# MAGI_sPrototypeBoard.net
KiCad netlist of a schematic drawn in Altium Designer
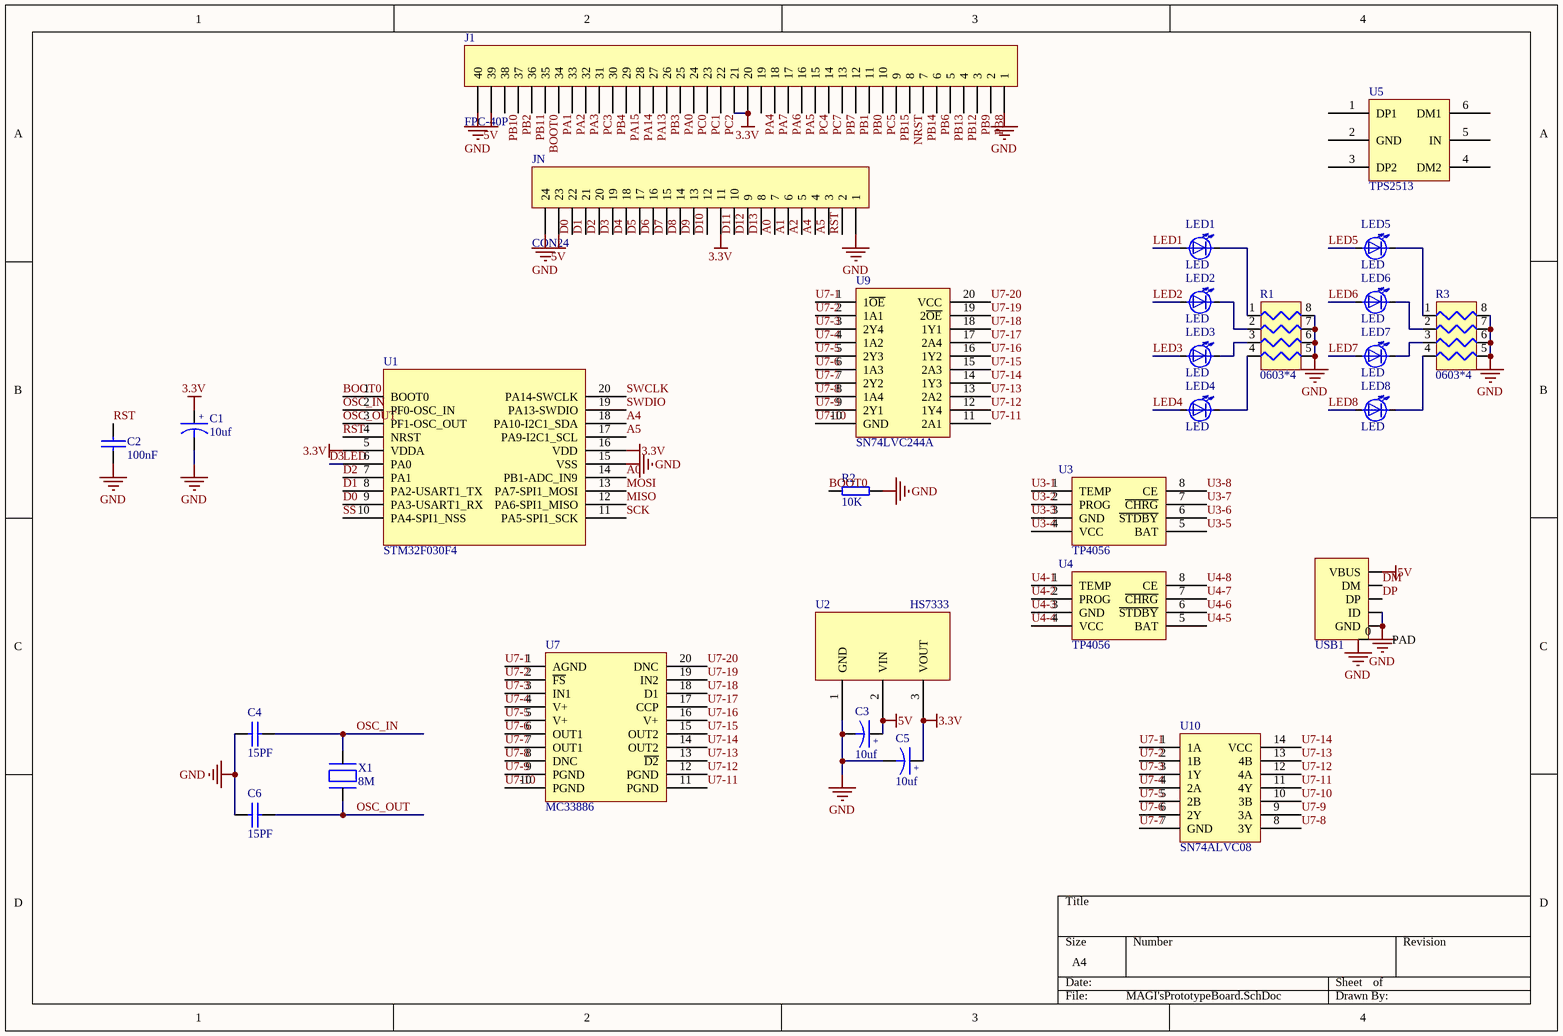
[diagram p0: MAGI'sPrototypeBoard.SchDoc]

(export (version "E")
  (design (tool "Eeschema 10.0.6"))
  (components
    (comp (ref "C1")
      (value "10uf")
      (footprint "6-0805_n")
      (description "Capacitor")
      (libsource (lib "电容器") (part "CAPACITOR POL"))
    )
    (comp (ref "C2") (value "100nF") (footprint "6-0805_n") (libsource (lib "STM32") (part "CAP")))
    (comp (ref "C3")
      (value "10uf")
      (footprint "6-0805_n")
      (description "Capacitor")
      (libsource (lib "电容器") (part "CAPACITOR POL"))
    )
    (comp (ref "C4") (value "15PF") (footprint "6-0805_n") (libsource (lib "STM32") (part "CAP")))
    (comp (ref "C5")
      (value "10uf")
      (footprint "6-0805_n")
      (description "Capacitor")
      (libsource (lib "电容器") (part "CAPACITOR POL"))
    )
    (comp (ref "C6") (value "15PF") (footprint "6-0805_n") (libsource (lib "STM32") (part "CAP")))
    (comp (ref "J1")
      (value "FPC-40P")
      (footprint "FFC/SM0.5-2H40")
      (description "Connector")
      (libsource (lib "CON系列") (part "CON40"))
    )
    (comp (ref "JN")
      (value "CON24")
      (footprint "FFC/SM0.5-2H24")
      (description "Connector")
      (libsource (lib "CON系列") (part "CON24"))
    )
    (comp (ref "LED1") (value "LED") (footprint "6-0805_N") (libsource (lib "二极管") (part "LED_3")))
    (comp (ref "LED2") (value "LED") (footprint "6-0805_N") (libsource (lib "二极管") (part "LED_3")))
    (comp (ref "LED3") (value "LED") (footprint "6-0805_N") (libsource (lib "二极管") (part "LED_3")))
    (comp (ref "LED4") (value "LED") (footprint "6-0805_N") (libsource (lib "二极管") (part "LED_3")))
    (comp (ref "LED5") (value "LED") (footprint "6-0805_N") (libsource (lib "二极管") (part "LED_3")))
    (comp (ref "LED6") (value "LED") (footprint "6-0805_N") (libsource (lib "二极管") (part "LED_3")))
    (comp (ref "LED7") (value "LED") (footprint "6-0805_N") (libsource (lib "二极管") (part "LED_3")))
    (comp (ref "LED8") (value "LED") (footprint "6-0805_N") (libsource (lib "二极管") (part "LED_3")))
    (comp (ref "R1") (value "0603*4") (footprint "0603*4") (libsource (lib "Res") (part "0603*4")))
    (comp (ref "R2") (value "10K") (footprint "6-0805_n") (libsource (lib "STM32") (part "RES")))
    (comp (ref "R3") (value "0603*4") (footprint "0603*4") (libsource (lib "Res") (part "0603*4")))
    (comp (ref "U1")
      (value "STM32F030F4")
      (footprint "STM32F030")
      (libsource (lib "MCU") (part "STM32F030F4"))
    )
    (comp (ref "U2") (value "HS7333") (footprint "HS7333") (libsource (lib "PMIC") (part "HS7333")))
    (comp (ref "U3") (value "TP4056") (footprint "TP4056") (libsource (lib "PMIC") (part "TP4056")))
    (comp (ref "U4") (value "TP4056") (footprint "TP4056") (libsource (lib "PMIC") (part "TP4056")))
    (comp (ref "U5") (value "TPS2513") (footprint "TPS2513") (libsource (lib "PMIC") (part "TPS2513")))
    (comp (ref "U7") (value "MC33886") (footprint "MC33886") (libsource (lib "PMIC") (part "MC33886")))
    (comp (ref "U9")
      (value "SN74LVC244A")
      (footprint "TPS61030PWP")
      (libsource (lib "LogicIC") (part "74LVC244"))
    )
    (comp (ref "U10")
      (value "SN74ALVC08")
      (footprint "SN74ALVC08D")
      (libsource (lib "LogicIC") (part "SN74ALVC08"))
    )
    (comp (ref "USB1")
      (value "USB_Micro")
      (footprint "USB:MicroUSB-B")
      (description "USB")
      (libsource (lib "SCH_USB") (part "USB_Micro"))
    )
    (comp (ref "X1") (value "8M") (footprint "5032") (libsource (lib "STM32") (part "CRYSTAL")))
  )
  (nets
    (net (code "1") (name "/A0") (class "Default")
      (node (ref "JN") (pin "7") (pinfunction "7_7") (pintype "passive"))
      (node (ref "U1") (pin "14") (pinfunction "PB1-ADC_IN9_14") (pintype "passive"))
    )
    (net (code "2") (name "/A1") (class "Default")
      (node (ref "JN") (pin "6") (pinfunction "6_6") (pintype "passive"))
    )
    (net (code "3") (name "/A2") (class "Default")
      (node (ref "JN") (pin "5") (pinfunction "5_5") (pintype "passive"))
    )
    (net (code "4") (name "/A4") (class "Default")
      (node (ref "JN") (pin "4") (pinfunction "4_4") (pintype "passive"))
      (node (ref "U1") (pin "18") (pinfunction "PA10-I2C1_SDA_18") (pintype "passive"))
    )
    (net (code "5") (name "/A5") (class "Default")
      (node (ref "JN") (pin "3") (pinfunction "3_3") (pintype "passive"))
      (node (ref "U1") (pin "17") (pinfunction "PA9-I2C1_SCL_17") (pintype "passive"))
    )
    (net (code "6") (name "/BOOT0") (class "Default")
      (node (ref "J1") (pin "35") (pinfunction "35_35") (pintype "passive"))
      (node (ref "R2") (pin "2") (pinfunction "2_2") (pintype "passive"))
      (node (ref "U1") (pin "1") (pinfunction "BOOT0_1") (pintype "passive"))
    )
    (net (code "7") (name "/D0") (class "Default")
      (node (ref "JN") (pin "22") (pinfunction "22_22") (pintype "passive"))
      (node (ref "U1") (pin "9") (pinfunction "PA3-USART1_RX_9") (pintype "passive"))
    )
    (net (code "8") (name "/D1") (class "Default")
      (node (ref "JN") (pin "21") (pinfunction "21_21") (pintype "passive"))
      (node (ref "U1") (pin "8") (pinfunction "PA2-USART1_TX_8") (pintype "passive"))
    )
    (net (code "9") (name "/D2") (class "Default")
      (node (ref "JN") (pin "20") (pinfunction "20_20") (pintype "passive"))
      (node (ref "U1") (pin "7") (pinfunction "PA1_7") (pintype "passive"))
    )
    (net (code "10") (name "/D3") (class "Default")
      (node (ref "JN") (pin "19") (pinfunction "19_19") (pintype "passive"))
      (node (ref "U1") (pin "6") (pinfunction "PA0_6") (pintype "passive"))
    )
    (net (code "11") (name "/D4") (class "Default")
      (node (ref "JN") (pin "18") (pinfunction "18_18") (pintype "passive"))
    )
    (net (code "12") (name "/D5") (class "Default")
      (node (ref "JN") (pin "17") (pinfunction "17_17") (pintype "passive"))
    )
    (net (code "13") (name "/D6") (class "Default")
      (node (ref "JN") (pin "16") (pinfunction "16_16") (pintype "passive"))
    )
    (net (code "14") (name "/D7") (class "Default")
      (node (ref "JN") (pin "15") (pinfunction "15_15") (pintype "passive"))
    )
    (net (code "15") (name "/D8") (class "Default")
      (node (ref "JN") (pin "14") (pinfunction "14_14") (pintype "passive"))
    )
    (net (code "16") (name "/D9") (class "Default")
      (node (ref "JN") (pin "13") (pinfunction "13_13") (pintype "passive"))
    )
    (net (code "17") (name "/D10") (class "Default")
      (node (ref "JN") (pin "12") (pinfunction "12_12") (pintype "passive"))
    )
    (net (code "18") (name "/D11") (class "Default")
      (node (ref "JN") (pin "10") (pinfunction "10_10") (pintype "passive"))
    )
    (net (code "19") (name "/D12") (class "Default")
      (node (ref "JN") (pin "9") (pinfunction "9_9") (pintype "passive"))
    )
    (net (code "20") (name "/D13") (class "Default")
      (node (ref "JN") (pin "8") (pinfunction "8_8") (pintype "passive"))
    )
    (net (code "21") (name "/DM") (class "Default")
      (node (ref "USB1") (pin "2") (pinfunction "DM_2") (pintype "passive"))
    )
    (net (code "22") (name "/DP") (class "Default")
      (node (ref "USB1") (pin "3") (pinfunction "DP_3") (pintype "passive"))
    )
    (net (code "23") (name "/LED1") (class "Default")
      (node (ref "LED1") (pin "1") (pinfunction "A_1") (pintype "passive"))
    )
    (net (code "24") (name "/LED2") (class "Default")
      (node (ref "LED2") (pin "1") (pinfunction "A_1") (pintype "passive"))
    )
    (net (code "25") (name "/LED3") (class "Default")
      (node (ref "LED3") (pin "1") (pinfunction "A_1") (pintype "passive"))
    )
    (net (code "26") (name "/LED4") (class "Default")
      (node (ref "LED4") (pin "1") (pinfunction "A_1") (pintype "passive"))
    )
    (net (code "27") (name "/LED5") (class "Default")
      (node (ref "LED5") (pin "1") (pinfunction "A_1") (pintype "passive"))
    )
    (net (code "28") (name "/LED6") (class "Default")
      (node (ref "LED6") (pin "1") (pinfunction "A_1") (pintype "passive"))
    )
    (net (code "29") (name "/LED7") (class "Default")
      (node (ref "LED7") (pin "1") (pinfunction "A_1") (pintype "passive"))
    )
    (net (code "30") (name "/LED8") (class "Default")
      (node (ref "LED8") (pin "1") (pinfunction "A_1") (pintype "passive"))
    )
    (net (code "31") (name "/MISO") (class "Default")
      (node (ref "U1") (pin "12") (pinfunction "PA6-SPI1_MISO_12") (pintype "passive"))
    )
    (net (code "32") (name "/MOSI") (class "Default")
      (node (ref "U1") (pin "13") (pinfunction "PA7-SPI1_MOSI_13") (pintype "passive"))
    )
    (net (code "33") (name "/NRST") (class "Default")
      (node (ref "J1") (pin "8") (pinfunction "8_8") (pintype "passive"))
    )
    (net (code "34") (name "/OSC_IN") (class "Default")
      (node (ref "C4") (pin "2") (pinfunction "2_2") (pintype "passive"))
      (node (ref "U1") (pin "2") (pinfunction "PF0-OSC_IN_2") (pintype "passive"))
      (node (ref "X1") (pin "1") (pinfunction "1_1") (pintype "passive"))
    )
    (net (code "35") (name "/OSC_OUT") (class "Default")
      (node (ref "C6") (pin "2") (pinfunction "2_2") (pintype "passive"))
      (node (ref "U1") (pin "3") (pinfunction "PF1-OSC_OUT_3") (pintype "passive"))
      (node (ref "X1") (pin "2") (pinfunction "2_2") (pintype "passive"))
    )
    (net (code "36") (name "/PA0") (class "Default")
      (node (ref "J1") (pin "25") (pinfunction "25_25") (pintype "passive"))
    )
    (net (code "37") (name "/PA1") (class "Default")
      (node (ref "J1") (pin "34") (pinfunction "34_34") (pintype "passive"))
    )
    (net (code "38") (name "/PA2") (class "Default")
      (node (ref "J1") (pin "33") (pinfunction "33_33") (pintype "passive"))
    )
    (net (code "39") (name "/PA3") (class "Default")
      (node (ref "J1") (pin "32") (pinfunction "32_32") (pintype "passive"))
    )
    (net (code "40") (name "/PA4") (class "Default")
      (node (ref "J1") (pin "19") (pinfunction "19_19") (pintype "passive"))
    )
    (net (code "41") (name "/PA5") (class "Default")
      (node (ref "J1") (pin "16") (pinfunction "16_16") (pintype "passive"))
    )
    (net (code "42") (name "/PA6") (class "Default")
      (node (ref "J1") (pin "17") (pinfunction "17_17") (pintype "passive"))
    )
    (net (code "43") (name "/PA7") (class "Default")
      (node (ref "J1") (pin "18") (pinfunction "18_18") (pintype "passive"))
    )
    (net (code "44") (name "/PA13") (class "Default")
      (node (ref "J1") (pin "27") (pinfunction "27_27") (pintype "passive"))
    )
    (net (code "45") (name "/PA14") (class "Default")
      (node (ref "J1") (pin "28") (pinfunction "28_28") (pintype "passive"))
    )
    (net (code "46") (name "/PA15") (class "Default")
      (node (ref "J1") (pin "29") (pinfunction "29_29") (pintype "passive"))
    )
    (net (code "47") (name "/PB0") (class "Default")
      (node (ref "J1") (pin "11") (pinfunction "11_11") (pintype "passive"))
    )
    (net (code "48") (name "/PB1") (class "Default")
      (node (ref "J1") (pin "12") (pinfunction "12_12") (pintype "passive"))
    )
    (net (code "49") (name "/PB2") (class "Default")
      (node (ref "J1") (pin "37") (pinfunction "37_37") (pintype "passive"))
    )
    (net (code "50") (name "/PB3") (class "Default")
      (node (ref "J1") (pin "26") (pinfunction "26_26") (pintype "passive"))
    )
    (net (code "51") (name "/PB4") (class "Default")
      (node (ref "J1") (pin "30") (pinfunction "30_30") (pintype "passive"))
    )
    (net (code "52") (name "/PB6") (class "Default")
      (node (ref "J1") (pin "6") (pinfunction "6_6") (pintype "passive"))
    )
    (net (code "53") (name "/PB7") (class "Default")
      (node (ref "J1") (pin "13") (pinfunction "13_13") (pintype "passive"))
    )
    (net (code "54") (name "/PB8") (class "Default")
      (node (ref "J1") (pin "2") (pinfunction "2_2") (pintype "passive"))
    )
    (net (code "55") (name "/PB9") (class "Default")
      (node (ref "J1") (pin "3") (pinfunction "3_3") (pintype "passive"))
    )
    (net (code "56") (name "/PB10") (class "Default")
      (node (ref "J1") (pin "38") (pinfunction "38_38") (pintype "passive"))
    )
    (net (code "57") (name "/PB11") (class "Default")
      (node (ref "J1") (pin "36") (pinfunction "36_36") (pintype "passive"))
    )
    (net (code "58") (name "/PB12") (class "Default")
      (node (ref "J1") (pin "4") (pinfunction "4_4") (pintype "passive"))
    )
    (net (code "59") (name "/PB13") (class "Default")
      (node (ref "J1") (pin "5") (pinfunction "5_5") (pintype "passive"))
    )
    (net (code "60") (name "/PB14") (class "Default")
      (node (ref "J1") (pin "7") (pinfunction "7_7") (pintype "passive"))
    )
    (net (code "61") (name "/PB15") (class "Default")
      (node (ref "J1") (pin "9") (pinfunction "9_9") (pintype "passive"))
    )
    (net (code "62") (name "/PC0") (class "Default")
      (node (ref "J1") (pin "24") (pinfunction "24_24") (pintype "passive"))
    )
    (net (code "63") (name "/PC1") (class "Default")
      (node (ref "J1") (pin "23") (pinfunction "23_23") (pintype "passive"))
    )
    (net (code "64") (name "/PC2") (class "Default")
      (node (ref "J1") (pin "22") (pinfunction "22_22") (pintype "passive"))
    )
    (net (code "65") (name "/PC3") (class "Default")
      (node (ref "J1") (pin "31") (pinfunction "31_31") (pintype "passive"))
    )
    (net (code "66") (name "/PC4") (class "Default")
      (node (ref "J1") (pin "15") (pinfunction "15_15") (pintype "passive"))
    )
    (net (code "67") (name "/PC5") (class "Default")
      (node (ref "J1") (pin "10") (pinfunction "10_10") (pintype "passive"))
    )
    (net (code "68") (name "/PC7") (class "Default")
      (node (ref "J1") (pin "14") (pinfunction "14_14") (pintype "passive"))
    )
    (net (code "69") (name "/RST") (class "Default")
      (node (ref "C2") (pin "2") (pinfunction "2_2") (pintype "passive"))
      (node (ref "JN") (pin "2") (pinfunction "2_2") (pintype "passive"))
      (node (ref "U1") (pin "4") (pinfunction "NRST_4") (pintype "passive"))
    )
    (net (code "70") (name "/SCK") (class "Default")
      (node (ref "U1") (pin "11") (pinfunction "PA5-SPI1_SCK_11") (pintype "passive"))
    )
    (net (code "71") (name "/SS") (class "Default")
      (node (ref "U1") (pin "10") (pinfunction "PA4-SPI1_NSS_10") (pintype "passive"))
    )
    (net (code "72") (name "/SWCLK") (class "Default")
      (node (ref "U1") (pin "20") (pinfunction "PA14-SWCLK_20") (pintype "passive"))
    )
    (net (code "73") (name "/SWDIO") (class "Default")
      (node (ref "U1") (pin "19") (pinfunction "PA13-SWDIO_19") (pintype "passive"))
    )
    (net (code "74") (name "/U3-1") (class "Default")
      (node (ref "U3") (pin "1") (pinfunction "TEMP_1") (pintype "passive"))
    )
    (net (code "75") (name "/U3-2") (class "Default")
      (node (ref "U3") (pin "2") (pinfunction "PROG_2") (pintype "passive"))
    )
    (net (code "76") (name "/U3-3") (class "Default")
      (node (ref "U3") (pin "3") (pinfunction "GND_3") (pintype "passive"))
    )
    (net (code "77") (name "/U3-4") (class "Default")
      (node (ref "U3") (pin "4") (pinfunction "VCC_4") (pintype "passive"))
    )
    (net (code "78") (name "/U3-5") (class "Default")
      (node (ref "U3") (pin "5") (pinfunction "BAT_5") (pintype "passive"))
    )
    (net (code "79") (name "/U3-6") (class "Default")
      (node (ref "U3") (pin "6") (pinfunction "~{STDBY}_6") (pintype "passive"))
    )
    (net (code "80") (name "/U3-7") (class "Default")
      (node (ref "U3") (pin "7") (pinfunction "~{CHRG}_7") (pintype "passive"))
    )
    (net (code "81") (name "/U3-8") (class "Default")
      (node (ref "U3") (pin "8") (pinfunction "CE_8") (pintype "passive"))
    )
    (net (code "82") (name "/U4-1") (class "Default")
      (node (ref "U4") (pin "1") (pinfunction "TEMP_1") (pintype "passive"))
    )
    (net (code "83") (name "/U4-2") (class "Default")
      (node (ref "U4") (pin "2") (pinfunction "PROG_2") (pintype "passive"))
    )
    (net (code "84") (name "/U4-3") (class "Default")
      (node (ref "U4") (pin "3") (pinfunction "GND_3") (pintype "passive"))
    )
    (net (code "85") (name "/U4-4") (class "Default")
      (node (ref "U4") (pin "4") (pinfunction "VCC_4") (pintype "passive"))
    )
    (net (code "86") (name "/U4-5") (class "Default")
      (node (ref "U4") (pin "5") (pinfunction "BAT_5") (pintype "passive"))
    )
    (net (code "87") (name "/U4-6") (class "Default")
      (node (ref "U4") (pin "6") (pinfunction "~{STDBY}_6") (pintype "passive"))
    )
    (net (code "88") (name "/U4-7") (class "Default")
      (node (ref "U4") (pin "7") (pinfunction "~{CHRG}_7") (pintype "passive"))
    )
    (net (code "89") (name "/U4-8") (class "Default")
      (node (ref "U4") (pin "8") (pinfunction "CE_8") (pintype "passive"))
    )
    (net (code "90") (name "/U7-1") (class "Default")
      (node (ref "U10") (pin "1") (pinfunction "1A_1") (pintype "passive"))
      (node (ref "U7") (pin "1") (pinfunction "AGND_1") (pintype "passive"))
      (node (ref "U9") (pin "1") (pinfunction "1~{OE}_1") (pintype "passive"))
    )
    (net (code "91") (name "/U7-2") (class "Default")
      (node (ref "U10") (pin "2") (pinfunction "1B_2") (pintype "passive"))
      (node (ref "U7") (pin "2") (pinfunction "~{FS}_2") (pintype "passive"))
      (node (ref "U9") (pin "2") (pinfunction "1A1_2") (pintype "passive"))
    )
    (net (code "92") (name "/U7-3") (class "Default")
      (node (ref "U10") (pin "3") (pinfunction "1Y_3") (pintype "passive"))
      (node (ref "U7") (pin "3") (pinfunction "IN1_3") (pintype "passive"))
      (node (ref "U9") (pin "3") (pinfunction "2Y4_3") (pintype "passive"))
    )
    (net (code "93") (name "/U7-4") (class "Default")
      (node (ref "U10") (pin "4") (pinfunction "2A_4") (pintype "passive"))
      (node (ref "U7") (pin "4") (pinfunction "V+_4") (pintype "passive"))
      (node (ref "U9") (pin "4") (pinfunction "1A2_4") (pintype "passive"))
    )
    (net (code "94") (name "/U7-5") (class "Default")
      (node (ref "U10") (pin "5") (pinfunction "2B_5") (pintype "passive"))
      (node (ref "U7") (pin "5") (pinfunction "V+_5") (pintype "passive"))
      (node (ref "U9") (pin "5") (pinfunction "2Y3_5") (pintype "passive"))
    )
    (net (code "95") (name "/U7-6") (class "Default")
      (node (ref "U10") (pin "6") (pinfunction "2Y_6") (pintype "passive"))
      (node (ref "U7") (pin "6") (pinfunction "OUT1_6") (pintype "passive"))
      (node (ref "U9") (pin "6") (pinfunction "1A3_6") (pintype "passive"))
    )
    (net (code "96") (name "/U7-7") (class "Default")
      (node (ref "U10") (pin "7") (pinfunction "GND_7") (pintype "passive"))
      (node (ref "U7") (pin "7") (pinfunction "OUT1_7") (pintype "passive"))
      (node (ref "U9") (pin "7") (pinfunction "2Y2_7") (pintype "passive"))
    )
    (net (code "97") (name "/U7-8") (class "Default")
      (node (ref "U10") (pin "8") (pinfunction "3Y_8") (pintype "passive"))
      (node (ref "U7") (pin "8") (pinfunction "DNC_8") (pintype "passive"))
      (node (ref "U9") (pin "8") (pinfunction "1A4_8") (pintype "passive"))
    )
    (net (code "98") (name "/U7-9") (class "Default")
      (node (ref "U10") (pin "9") (pinfunction "3A_9") (pintype "passive"))
      (node (ref "U7") (pin "9") (pinfunction "PGND_9") (pintype "passive"))
      (node (ref "U9") (pin "9") (pinfunction "2Y1_9") (pintype "passive"))
    )
    (net (code "99") (name "/U7-10") (class "Default")
      (node (ref "U10") (pin "10") (pinfunction "3B_10") (pintype "passive"))
      (node (ref "U7") (pin "10") (pinfunction "PGND_10") (pintype "passive"))
      (node (ref "U9") (pin "10") (pinfunction "GND_10") (pintype "passive"))
    )
    (net (code "100") (name "/U7-11") (class "Default")
      (node (ref "U10") (pin "11") (pinfunction "4Y_11") (pintype "passive"))
      (node (ref "U7") (pin "11") (pinfunction "PGND_11") (pintype "passive"))
      (node (ref "U9") (pin "11") (pinfunction "2A1_11") (pintype "passive"))
    )
    (net (code "101") (name "/U7-12") (class "Default")
      (node (ref "U10") (pin "12") (pinfunction "4A_12") (pintype "passive"))
      (node (ref "U7") (pin "12") (pinfunction "PGND_12") (pintype "passive"))
      (node (ref "U9") (pin "12") (pinfunction "1Y4_12") (pintype "passive"))
    )
    (net (code "102") (name "/U7-13") (class "Default")
      (node (ref "U10") (pin "13") (pinfunction "4B_13") (pintype "passive"))
      (node (ref "U7") (pin "13") (pinfunction "~{D2}_13") (pintype "passive"))
      (node (ref "U9") (pin "13") (pinfunction "2A2_13") (pintype "passive"))
    )
    (net (code "103") (name "/U7-14") (class "Default")
      (node (ref "U10") (pin "14") (pinfunction "VCC_14") (pintype "passive"))
      (node (ref "U7") (pin "14") (pinfunction "OUT2_14") (pintype "passive"))
      (node (ref "U9") (pin "14") (pinfunction "1Y3_14") (pintype "passive"))
    )
    (net (code "104") (name "/U7-15") (class "Default")
      (node (ref "U7") (pin "15") (pinfunction "OUT2_15") (pintype "passive"))
      (node (ref "U9") (pin "15") (pinfunction "2A3_15") (pintype "passive"))
    )
    (net (code "105") (name "/U7-16") (class "Default")
      (node (ref "U7") (pin "16") (pinfunction "V+_16") (pintype "passive"))
      (node (ref "U9") (pin "16") (pinfunction "1Y2_16") (pintype "passive"))
    )
    (net (code "106") (name "/U7-17") (class "Default")
      (node (ref "U7") (pin "17") (pinfunction "CCP_17") (pintype "passive"))
      (node (ref "U9") (pin "17") (pinfunction "2A4_17") (pintype "passive"))
    )
    (net (code "107") (name "/U7-18") (class "Default")
      (node (ref "U7") (pin "18") (pinfunction "D1_18") (pintype "passive"))
      (node (ref "U9") (pin "18") (pinfunction "1Y1_18") (pintype "passive"))
    )
    (net (code "108") (name "/U7-19") (class "Default")
      (node (ref "U7") (pin "19") (pinfunction "IN2_19") (pintype "passive"))
      (node (ref "U9") (pin "19") (pinfunction "2~{OE}_19") (pintype "passive"))
    )
    (net (code "109") (name "/U7-20") (class "Default")
      (node (ref "U7") (pin "20") (pinfunction "DNC_20") (pintype "passive"))
      (node (ref "U9") (pin "20") (pinfunction "VCC_20") (pintype "passive"))
    )
    (net (code "110") (name "3.3V") (class "Default")
      (node (ref "C1") (pin "1") (pinfunction "1_1") (pintype "passive"))
      (node (ref "C5") (pin "1") (pinfunction "1_1") (pintype "passive"))
      (node (ref "J1") (pin "20") (pinfunction "20_20") (pintype "passive"))
      (node (ref "J1") (pin "21") (pinfunction "21_21") (pintype "passive"))
      (node (ref "JN") (pin "11") (pinfunction "11_11") (pintype "passive"))
      (node (ref "U1") (pin "16") (pinfunction "VDD_16") (pintype "passive"))
      (node (ref "U1") (pin "5") (pinfunction "VDDA_5") (pintype "passive"))
      (node (ref "U2") (pin "3") (pinfunction "VOUT_3") (pintype "passive"))
    )
    (net (code "111") (name "5V") (class "Default")
      (node (ref "C3") (pin "1") (pinfunction "1_1") (pintype "passive"))
      (node (ref "J1") (pin "39") (pinfunction "39_39") (pintype "passive"))
      (node (ref "JN") (pin "23") (pinfunction "23_23") (pintype "passive"))
      (node (ref "U2") (pin "2") (pinfunction "VIN_2") (pintype "passive"))
      (node (ref "USB1") (pin "1") (pinfunction "VBUS_1") (pintype "passive"))
    )
    (net (code "112") (name "GND") (class "Default")
      (node (ref "C1") (pin "2") (pinfunction "2_2") (pintype "passive"))
      (node (ref "C2") (pin "1") (pinfunction "1_1") (pintype "passive"))
      (node (ref "C3") (pin "2") (pinfunction "2_2") (pintype "passive"))
      (node (ref "C4") (pin "1") (pinfunction "1_1") (pintype "passive"))
      (node (ref "C5") (pin "2") (pinfunction "2_2") (pintype "passive"))
      (node (ref "C6") (pin "1") (pinfunction "1_1") (pintype "passive"))
      (node (ref "J1") (pin "1") (pinfunction "1_1") (pintype "passive"))
      (node (ref "J1") (pin "40") (pinfunction "40_40") (pintype "passive"))
      (node (ref "JN") (pin "1") (pinfunction "1_1") (pintype "passive"))
      (node (ref "JN") (pin "24") (pinfunction "24_24") (pintype "passive"))
      (node (ref "R1") (pin "5") (pintype "passive"))
      (node (ref "R1") (pin "6") (pintype "passive"))
      (node (ref "R1") (pin "7") (pintype "passive"))
      (node (ref "R1") (pin "8") (pintype "passive"))
      (node (ref "R2") (pin "1") (pinfunction "1_1") (pintype "passive"))
      (node (ref "R3") (pin "5") (pintype "passive"))
      (node (ref "R3") (pin "6") (pintype "passive"))
      (node (ref "R3") (pin "7") (pintype "passive"))
      (node (ref "R3") (pin "8") (pintype "passive"))
      (node (ref "U1") (pin "15") (pinfunction "VSS_15") (pintype "passive"))
      (node (ref "U2") (pin "1") (pinfunction "GND_1") (pintype "passive"))
      (node (ref "USB1") (pin "0") (pinfunction "PAD_0") (pintype "passive"))
      (node (ref "USB1") (pin "4") (pinfunction "ID_4") (pintype "passive"))
      (node (ref "USB1") (pin "5") (pinfunction "GND_5") (pintype "passive"))
    )
    (net (code "113") (name "Net-(LED1-K)") (class "Default")
      (node (ref "LED1") (pin "2") (pinfunction "K_2") (pintype "passive"))
      (node (ref "R1") (pin "1") (pintype "passive"))
    )
    (net (code "114") (name "Net-(LED2-K)") (class "Default")
      (node (ref "LED2") (pin "2") (pinfunction "K_2") (pintype "passive"))
      (node (ref "R1") (pin "2") (pintype "passive"))
    )
    (net (code "115") (name "Net-(LED3-K)") (class "Default")
      (node (ref "LED3") (pin "2") (pinfunction "K_2") (pintype "passive"))
      (node (ref "R1") (pin "3") (pintype "passive"))
    )
    (net (code "116") (name "Net-(LED4-K)") (class "Default")
      (node (ref "LED4") (pin "2") (pinfunction "K_2") (pintype "passive"))
      (node (ref "R1") (pin "4") (pintype "passive"))
    )
    (net (code "117") (name "Net-(LED5-K)") (class "Default")
      (node (ref "LED5") (pin "2") (pinfunction "K_2") (pintype "passive"))
      (node (ref "R3") (pin "1") (pintype "passive"))
    )
    (net (code "118") (name "Net-(LED6-K)") (class "Default")
      (node (ref "LED6") (pin "2") (pinfunction "K_2") (pintype "passive"))
      (node (ref "R3") (pin "2") (pintype "passive"))
    )
    (net (code "119") (name "Net-(LED7-K)") (class "Default")
      (node (ref "LED7") (pin "2") (pinfunction "K_2") (pintype "passive"))
      (node (ref "R3") (pin "3") (pintype "passive"))
    )
    (net (code "120") (name "Net-(LED8-K)") (class "Default")
      (node (ref "LED8") (pin "2") (pinfunction "K_2") (pintype "passive"))
      (node (ref "R3") (pin "4") (pintype "passive"))
    )
    (net (code "121") (name "unconnected-(U5-DM1-Pad6)") (class "Default")
      (node (ref "U5") (pin "6") (pinfunction "DM1_6") (pintype "passive"))
    )
    (net (code "122") (name "unconnected-(U5-DM2-Pad4)") (class "Default")
      (node (ref "U5") (pin "4") (pinfunction "DM2_4") (pintype "passive"))
    )
    (net (code "123") (name "unconnected-(U5-DP1-Pad1)") (class "Default")
      (node (ref "U5") (pin "1") (pinfunction "DP1_1") (pintype "passive"))
    )
    (net (code "124") (name "unconnected-(U5-DP2-Pad3)") (class "Default")
      (node (ref "U5") (pin "3") (pinfunction "DP2_3") (pintype "passive"))
    )
    (net (code "125") (name "unconnected-(U5-GND-Pad2)") (class "Default")
      (node (ref "U5") (pin "2") (pinfunction "GND_2") (pintype "passive"))
    )
    (net (code "126") (name "unconnected-(U5-IN-Pad5)") (class "Default")
      (node (ref "U5") (pin "5") (pinfunction "IN_5") (pintype "passive"))
    )
  )
)
